# FC_GC_PCB.net
KiCad netlist of a schematic drawn in EasyEDA Pro
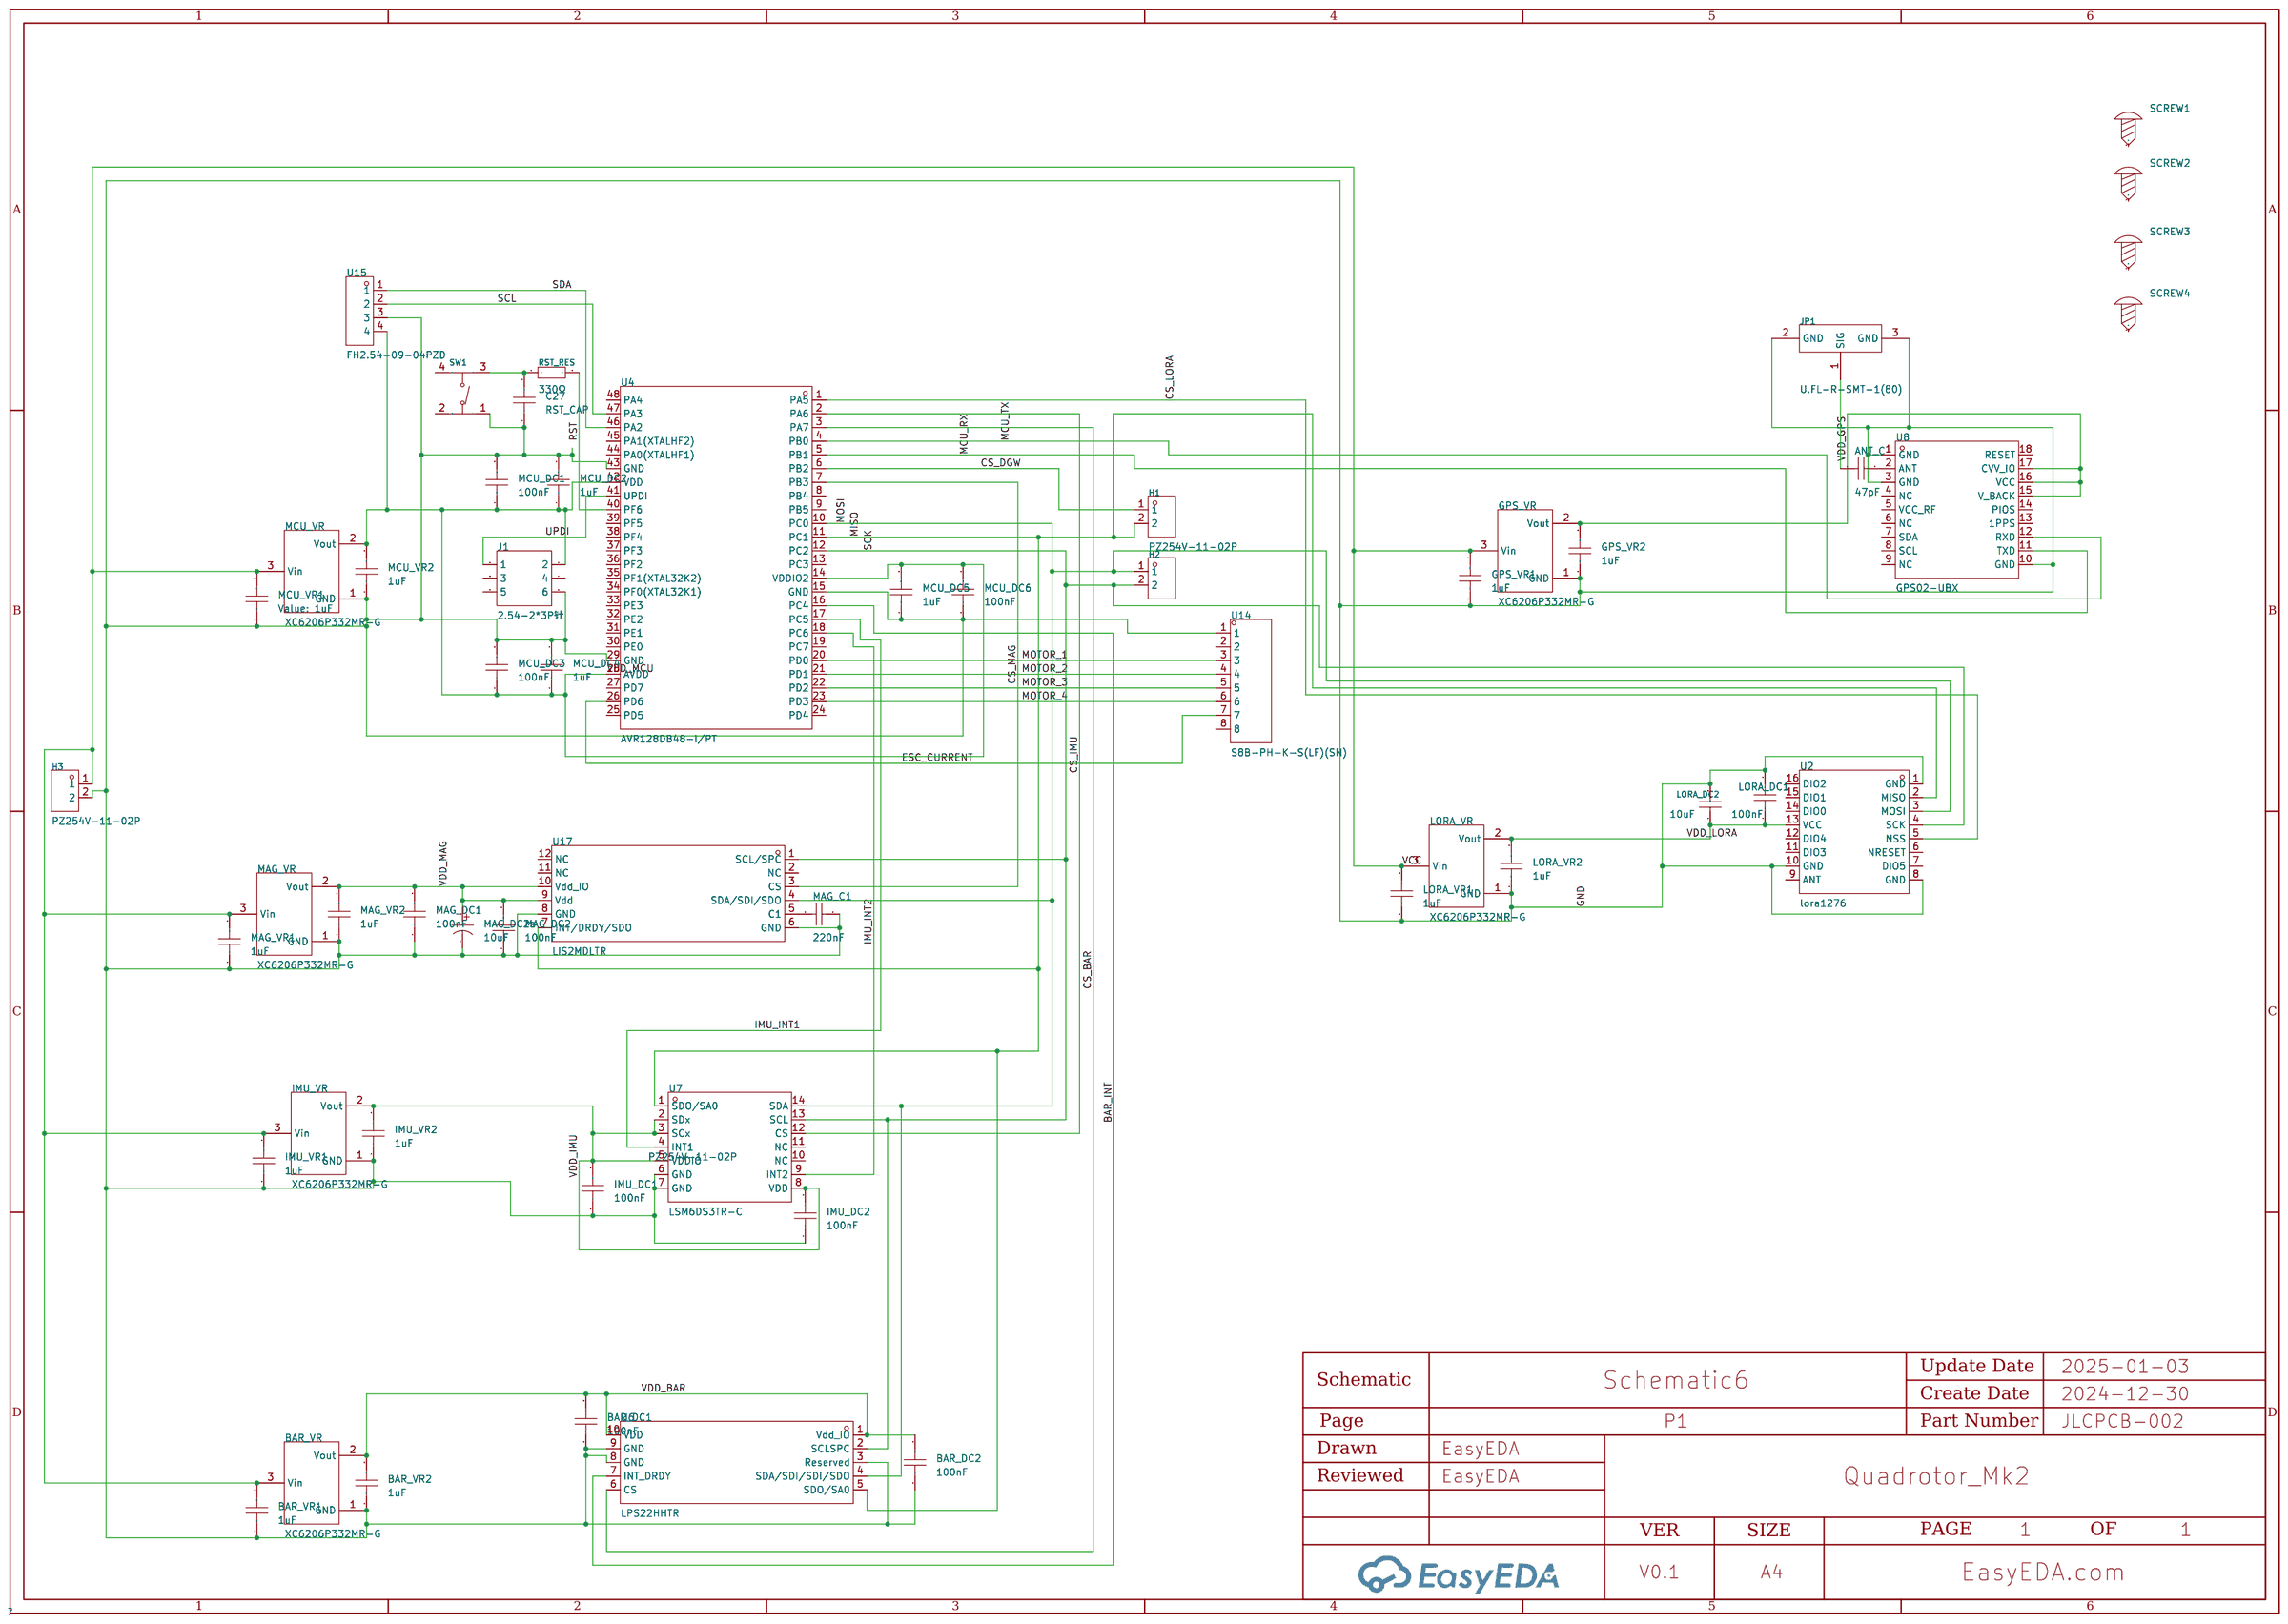
[diagram p0: schematic sheet]

(export (version "E")
  (design (tool "Eeschema 10.0.6"))
  (components
    (comp (ref "ANT_C")
      (value "47pF")
      (footprint "easyedapro:C0402")
      (fields (field (name "Manufacturer Part") "0402CG470J500NT") (field (name "Manufacturer") "FH(风华)"))
      (libsource (lib "easyedapro") (part "0402CG470J500NT"))
    )
    (comp (ref "BAR_DC1")
      (value "100nF")
      (footprint "easyedapro:C0402")
      (fields
        (field (name "Manufacturer Part") "CL05B104KO5NNNC")
        (field (name "Manufacturer") "SAMSUNG(三星)")
      )
      (libsource (lib "easyedapro") (part "CL05B104KO5NNNC"))
    )
    (comp (ref "BAR_DC2")
      (value "100nF")
      (footprint "easyedapro:C0402")
      (fields
        (field (name "Manufacturer Part") "CL05B104KO5NNNC")
        (field (name "Manufacturer") "SAMSUNG(三星)")
      )
      (libsource (lib "easyedapro") (part "CL05B104KO5NNNC"))
    )
    (comp (ref "BAR_VR")
      (value "XC6206P332MR-G")
      (footprint "easyedapro:SOT-23-3_L2.9-W1.6-P1.90-LS2.8-BR")
      (fields (field (name "Manufacturer") "TOREX(特瑞仕)"))
      (libsource (lib "easyedapro") (part "XC6206P332MR"))
    )
    (comp (ref "BAR_VR1")
      (value "1uF")
      (footprint "easyedapro:C0603")
      (fields
        (field (name "Manufacturer Part") "CL05A105KA5NQNC")
        (field (name "Manufacturer") "SAMSUNG(三星)")
      )
      (libsource (lib "easyedapro") (part "CL10A105KB8NNNC"))
    )
    (comp (ref "BAR_VR2")
      (value "1uF")
      (footprint "easyedapro:C0603")
      (fields
        (field (name "Manufacturer Part") "CL05A105KA5NQNC")
        (field (name "Manufacturer") "SAMSUNG(三星)")
      )
      (libsource (lib "easyedapro") (part "CL10A105KB8NNNC"))
    )
    (comp (ref "C27")
      (value "1uF")
      (footprint "easyedapro:C0603")
      (fields
        (field (name "Manufacturer Part") "CL10A105KB8NNNC")
        (field (name "Manufacturer") "SAMSUNG(三星)")
      )
      (libsource (lib "easyedapro") (part "CL10A105KB8NNNC"))
    )
    (comp (ref "GPS_VR")
      (value "XC6206P332MR-G")
      (footprint "easyedapro:SOT-23-3_L2.9-W1.6-P1.90-LS2.8-BR")
      (fields (field (name "Manufacturer") "TOREX(特瑞仕)"))
      (libsource (lib "easyedapro") (part "XC6206P332MR"))
    )
    (comp (ref "GPS_VR1")
      (value "1uF")
      (footprint "easyedapro:C0603")
      (fields
        (field (name "Manufacturer Part") "CL05A105KA5NQNC")
        (field (name "Manufacturer") "SAMSUNG(三星)")
      )
      (libsource (lib "easyedapro") (part "CL10A105KB8NNNC"))
    )
    (comp (ref "GPS_VR2")
      (value "1uF")
      (footprint "easyedapro:C0603")
      (fields
        (field (name "Manufacturer Part") "CL05A105KA5NQNC")
        (field (name "Manufacturer") "SAMSUNG(三星)")
      )
      (libsource (lib "easyedapro") (part "CL10A105KB8NNNC"))
    )
    (comp (ref "H1")
      (value "PZ254V-11-02P")
      (footprint "easyedapro:HDR-TH_2P-P2.54-V-M")
      (fields (field (name "Manufacturer") "XFCN(兴飞)"))
      (libsource (lib "easyedapro") (part "PZ254V-11-02P"))
    )
    (comp (ref "H2")
      (value "PZ254V-11-02P")
      (footprint "easyedapro:HDR-TH_2P-P2.54-V-M")
      (fields (field (name "Manufacturer") "XFCN(兴飞)"))
      (libsource (lib "easyedapro") (part "PZ254V-11-02P"))
    )
    (comp (ref "H3")
      (value "PZ254V-11-02P")
      (footprint "easyedapro:HDR-TH_2P-P2.54-V-M")
      (fields (field (name "Manufacturer") "XFCN(兴飞)"))
      (libsource (lib "easyedapro") (part "PZ254V-11-02P"))
    )
    (comp (ref "IMU_DC1")
      (value "100nF")
      (footprint "easyedapro:C0402")
      (fields
        (field (name "Manufacturer Part") "CL05B104KO5NNNC")
        (field (name "Manufacturer") "SAMSUNG(三星)")
      )
      (libsource (lib "easyedapro") (part "CL05B104KO5NNNC"))
    )
    (comp (ref "IMU_DC2")
      (value "100nF")
      (footprint "easyedapro:C0402")
      (fields
        (field (name "Manufacturer Part") "CL05B104KO5NNNC")
        (field (name "Manufacturer") "SAMSUNG(三星)")
      )
      (libsource (lib "easyedapro") (part "CL05B104KO5NNNC"))
    )
    (comp (ref "IMU_VR")
      (value "XC6206P332MR-G")
      (footprint "easyedapro:SOT-23-3_L2.9-W1.6-P1.90-LS2.8-BR")
      (fields (field (name "Manufacturer") "TOREX(特瑞仕)"))
      (libsource (lib "easyedapro") (part "XC6206P332MR"))
    )
    (comp (ref "IMU_VR1")
      (value "1uF")
      (footprint "easyedapro:C0603")
      (fields
        (field (name "Manufacturer Part") "CL05A105KA5NQNC")
        (field (name "Manufacturer") "SAMSUNG(三星)")
      )
      (libsource (lib "easyedapro") (part "CL10A105KB8NNNC"))
    )
    (comp (ref "IMU_VR2")
      (value "1uF")
      (footprint "easyedapro:C0603")
      (fields
        (field (name "Manufacturer Part") "CL05A105KA5NQNC")
        (field (name "Manufacturer") "SAMSUNG(三星)")
      )
      (libsource (lib "easyedapro") (part "CL10A105KB8NNNC"))
    )
    (comp (ref "J1")
      (value "2.54-2*3P针")
      (footprint "easyedapro:HDR-TH_6P-P2.54-V-M-R2-C3-S2.54-1")
      (fields (field (name "Manufacturer") "BOOMELE(博穆精密)"))
      (libsource (lib "easyedapro") (part "Header-Male-2.54_2x3"))
    )
    (comp (ref "JP1")
      (value "U.FL-R-SMT-1(80)")
      (footprint "easyedapro:RF-SMD_FRF05002-JSS103M")
      (fields (field (name "Manufacturer") "HRS(广濑)"))
      (libsource (lib "easyedapro") (part "U.FL-R-SMT-1(80)"))
    )
    (comp (ref "LORA_DC1")
      (value "100nF")
      (footprint "easyedapro:C0402")
      (fields
        (field (name "Manufacturer Part") "CL05B104KO5NNNC")
        (field (name "Manufacturer") "SAMSUNG(三星)")
      )
      (libsource (lib "easyedapro") (part "CL05B104KO5NNNC"))
    )
    (comp (ref "LORA_DC2")
      (value "10uF")
      (footprint "easyedapro:C0402")
      (fields
        (field (name "Manufacturer Part") "CL05A106MQ5NUNC")
        (field (name "Manufacturer") "SAMSUNG(三星)")
      )
      (libsource (lib "easyedapro") (part "CL05A106MQ5NUNC"))
    )
    (comp (ref "LORA_VR")
      (value "XC6206P332MR-G")
      (footprint "easyedapro:SOT-23-3_L2.9-W1.6-P1.90-LS2.8-BR")
      (fields (field (name "Manufacturer") "TOREX(特瑞仕)"))
      (libsource (lib "easyedapro") (part "XC6206P332MR"))
    )
    (comp (ref "LORA_VR1")
      (value "1uF")
      (footprint "easyedapro:C0603")
      (fields
        (field (name "Manufacturer Part") "CL05A105KA5NQNC")
        (field (name "Manufacturer") "SAMSUNG(三星)")
      )
      (libsource (lib "easyedapro") (part "CL10A105KB8NNNC"))
    )
    (comp (ref "LORA_VR2")
      (value "1uF")
      (footprint "easyedapro:C0603")
      (fields
        (field (name "Manufacturer Part") "CL05A105KA5NQNC")
        (field (name "Manufacturer") "SAMSUNG(三星)")
      )
      (libsource (lib "easyedapro") (part "CL10A105KB8NNNC"))
    )
    (comp (ref "MAG_C1")
      (value "220nF")
      (footprint "easyedapro:C0402")
      (fields
        (field (name "Manufacturer Part") "CL05B224KO5NNNC")
        (field (name "Manufacturer") "SAMSUNG(三星)")
      )
      (libsource (lib "easyedapro") (part "CL05B224KO5NNNC"))
    )
    (comp (ref "MAG_DC1")
      (value "100nF")
      (footprint "easyedapro:C0402")
      (fields
        (field (name "Manufacturer Part") "CL05B104KO5NNNC")
        (field (name "Manufacturer") "SAMSUNG(三星)")
      )
      (libsource (lib "easyedapro") (part "CL05B104KO5NNNC"))
    )
    (comp (ref "MAG_DC2")
      (value "100nF")
      (footprint "easyedapro:C0402")
      (fields
        (field (name "Manufacturer Part") "CL05B104KO5NNNC")
        (field (name "Manufacturer") "SAMSUNG(三星)")
      )
      (libsource (lib "easyedapro") (part "CL05B104KO5NNNC"))
    )
    (comp (ref "MAG_DC2a")
      (value "10uF")
      (fields (field (name "Manufacturer Part") "RVT1J100M0605") (field (name "Manufacturer") "ROQANG(容强)"))
      (libsource (lib "easyedapro") (part "HU2G100M-CRG12"))
    )
    (comp (ref "MAG_VR")
      (value "XC6206P332MR-G")
      (footprint "easyedapro:SOT-23-3_L2.9-W1.6-P1.90-LS2.8-BR")
      (fields (field (name "Manufacturer") "TOREX(特瑞仕)"))
      (libsource (lib "easyedapro") (part "XC6206P332MR"))
    )
    (comp (ref "MAG_VR1")
      (value "1uF")
      (footprint "easyedapro:C0603")
      (fields
        (field (name "Manufacturer Part") "CL05A105KA5NQNC")
        (field (name "Manufacturer") "SAMSUNG(三星)")
      )
      (libsource (lib "easyedapro") (part "CL10A105KB8NNNC"))
    )
    (comp (ref "MAG_VR2")
      (value "1uF")
      (footprint "easyedapro:C0603")
      (fields
        (field (name "Manufacturer Part") "CL05A105KA5NQNC")
        (field (name "Manufacturer") "SAMSUNG(三星)")
      )
      (libsource (lib "easyedapro") (part "CL10A105KB8NNNC"))
    )
    (comp (ref "MCU_DC1")
      (value "100nF")
      (footprint "easyedapro:C0402")
      (fields
        (field (name "Manufacturer Part") "CL05B104KO5NNNC")
        (field (name "Manufacturer") "SAMSUNG(三星)")
      )
      (libsource (lib "easyedapro") (part "CL05B104KO5NNNC"))
    )
    (comp (ref "MCU_DC2")
      (value "1uF")
      (footprint "easyedapro:C0603")
      (fields
        (field (name "Manufacturer Part") "CL05A105KA5NQNC")
        (field (name "Manufacturer") "SAMSUNG(三星)")
      )
      (libsource (lib "easyedapro") (part "CL10A105KB8NNNC"))
    )
    (comp (ref "MCU_DC3")
      (value "100nF")
      (footprint "easyedapro:C0402")
      (fields
        (field (name "Manufacturer Part") "CL05B104KO5NNNC")
        (field (name "Manufacturer") "SAMSUNG(三星)")
      )
      (libsource (lib "easyedapro") (part "CL05B104KO5NNNC"))
    )
    (comp (ref "MCU_DC4")
      (value "1uF")
      (footprint "easyedapro:C0603")
      (fields
        (field (name "Manufacturer Part") "CL05A105KA5NQNC")
        (field (name "Manufacturer") "SAMSUNG(三星)")
      )
      (libsource (lib "easyedapro") (part "CL10A105KB8NNNC"))
    )
    (comp (ref "MCU_DC5")
      (value "1uF")
      (footprint "easyedapro:C0603")
      (fields
        (field (name "Manufacturer Part") "CL05A105KA5NQNC")
        (field (name "Manufacturer") "SAMSUNG(三星)")
      )
      (libsource (lib "easyedapro") (part "CL10A105KB8NNNC"))
    )
    (comp (ref "MCU_DC6")
      (value "100nF")
      (footprint "easyedapro:C0402")
      (fields
        (field (name "Manufacturer Part") "CL05B104KO5NNNC")
        (field (name "Manufacturer") "SAMSUNG(三星)")
      )
      (libsource (lib "easyedapro") (part "CL05B104KO5NNNC"))
    )
    (comp (ref "MCU_VR")
      (value "XC6206P332MR-G")
      (footprint "easyedapro:SOT-23-3_L2.9-W1.6-P1.90-LS2.8-BR")
      (fields (field (name "Manufacturer") "TOREX(特瑞仕)"))
      (libsource (lib "easyedapro") (part "XC6206P332MR"))
    )
    (comp (ref "MCU_VR1")
      (value "1uF")
      (footprint "easyedapro:C0603")
      (fields
        (field (name "Manufacturer Part") "CL05A105KA5NQNC")
        (field (name "Manufacturer") "SAMSUNG(三星)")
      )
      (libsource (lib "easyedapro") (part "CL10A105KB8NNNC"))
    )
    (comp (ref "MCU_VR2")
      (value "1uF")
      (footprint "easyedapro:C0603")
      (fields
        (field (name "Manufacturer Part") "CL05A105KA5NQNC")
        (field (name "Manufacturer") "SAMSUNG(三星)")
      )
      (libsource (lib "easyedapro") (part "CL10A105KB8NNNC"))
    )
    (comp (ref "RST_RES")
      (value "330Ω")
      (footprint "easyedapro:R0402")
      (fields
        (field (name "Manufacturer Part") "0402WGF3300TCE")
        (field (name "Manufacturer") "UNI-ROYAL(厚声)")
      )
      (libsource (lib "easyedapro") (part "0402WGF3300TCE"))
    )
    (comp (ref "SCREW1")
      (value "~")
      (footprint "easyedapro:Screw-Hole-M2")
      (libsource (lib "easyedapro") (part "Screw-Hole"))
    )
    (comp (ref "SCREW2")
      (value "~")
      (footprint "easyedapro:Screw-Hole-M2")
      (libsource (lib "easyedapro") (part "Screw-Hole"))
    )
    (comp (ref "SCREW3")
      (value "~")
      (footprint "easyedapro:Screw-Hole-M2")
      (libsource (lib "easyedapro") (part "Screw-Hole"))
    )
    (comp (ref "SCREW4")
      (value "~")
      (footprint "easyedapro:Screw-Hole-M2")
      (libsource (lib "easyedapro") (part "Screw-Hole"))
    )
    (comp (ref "SW1")
      (value "TS-1187A-B-A-B")
      (footprint "easyedapro:SW-SMD_4P-L5.1-W5.1-P3.70-LS6.5-TL-2")
      (fields (field (name "Manufacturer") "XKB Connectivity(中国星坤)"))
      (libsource (lib "easyedapro") (part "TS-1187A-B-A-B"))
    )
    (comp (ref "U2")
      (value "lora1276")
      (footprint "easyedapro:COMM-SMD_LORA1276-C1-915MHZ")
      (description "Frequency:915MHz")
      (fields
        (field (name "Manufacturer Part") "lora1276-C1-915MHz")
        (field (name "Manufacturer") "G-NiceRF(思为无线)")
      )
      (libsource (lib "easyedapro") (part "LORA1276-C1-915MHZ"))
    )
    (comp (ref "U4")
      (value "AVR128DB48-I/PT")
      (footprint "easyedapro:TQFP-48_L7.0-W7.0-P0.50-LS9.0-BL")
      (fields (field (name "Manufacturer") "MICROCHIP(美国微芯)"))
      (libsource (lib "easyedapro") (part "AVR128DB48-I/PT"))
    )
    (comp (ref "U6")
      (value "LPS22HHTR")
      (footprint "easyedapro:HLGA-10L_LPS22HBTR")
      (fields (field (name "Manufacturer") "ST(意法半导体)"))
      (libsource (lib "easyedapro") (part "LPS22HHTR"))
    )
    (comp (ref "U7")
      (value "LSM6DS3TR-C")
      (footprint "easyedapro:LGA-14_L3.0-W2.5-P0.50-TL")
      (fields (field (name "Manufacturer") "ST(意法半导体)"))
      (libsource (lib "easyedapro") (part "LSM6DS3TR-C"))
    )
    (comp (ref "U8")
      (value "GPS02-UBX")
      (footprint "easyedapro:WIRELM-SMD_18P-L16.5-W14.5_P1.80-TL")
      (fields (field (name "Manufacturer") "G-NiceRF(思为无线)"))
      (libsource (lib "easyedapro") (part "GPS02-UBX"))
    )
    (comp (ref "U14")
      (value "S8B-PH-K-S(LF)(SN)")
      (footprint "easyedapro:CONN-TH_S8B-PH-K-S-LF-SN")
      (fields (field (name "Manufacturer") "JST"))
      (libsource (lib "easyedapro") (part "S8B-PH-K-S-(LF)(SN)"))
    )
    (comp (ref "U15")
      (value "FH2.54-09-04PZD")
      (footprint "easyedapro:HDR-TH_4P-P2.54-V-F")
      (fields (field (name "Manufacturer") "XUNPU(讯普)"))
      (libsource (lib "easyedapro") (part "FH2.54-09-04PZD"))
    )
    (comp (ref "U17")
      (value "LIS2MDLTR")
      (footprint "easyedapro:LGA-12_L2.0-W2.0-P0.50-BL")
      (fields (field (name "Manufacturer") "ST(意法半导体)"))
      (libsource (lib "easyedapro") (part "LIS2MDLTR"))
    )
  )
  (nets
    (net (code "1") (name "/BAR_INT") (class "Default")
      (node (ref "U4") (pin "16") (pinfunction "PC4_16") (pintype "unspecified"))
      (node (ref "U6") (pin "7") (pinfunction "INT_DRDY_7") (pintype "input"))
    )
    (net (code "2") (name "/CS_BAR") (class "Default")
      (node (ref "U4") (pin "3") (pinfunction "PA7_3") (pintype "unspecified"))
      (node (ref "U6") (pin "6") (pinfunction "CS_6") (pintype "input"))
    )
    (net (code "3") (name "/CS_DGW") (class "Default")
      (node (ref "H1") (pin "1") (pinfunction "1_1") (pintype "input"))
      (node (ref "U4") (pin "6") (pinfunction "PB2_6") (pintype "unspecified"))
    )
    (net (code "4") (name "/CS_IMU") (class "Default")
      (node (ref "U4") (pin "2") (pinfunction "PA6_2") (pintype "unspecified"))
      (node (ref "U7") (pin "12") (pinfunction "CS_12") (pintype "unspecified"))
    )
    (net (code "5") (name "/CS_LORA") (class "Default")
      (node (ref "U2") (pin "5") (pinfunction "NSS_5") (pintype "unspecified"))
      (node (ref "U4") (pin "1") (pinfunction "PA5_1") (pintype "unspecified"))
    )
    (net (code "6") (name "/CS_MAG") (class "Default")
      (node (ref "U17") (pin "3") (pinfunction "CS_3") (pintype "unspecified"))
      (node (ref "U4") (pin "7") (pinfunction "PB3_7") (pintype "unspecified"))
    )
    (net (code "7") (name "/ESC_CURRENT") (class "Default")
      (node (ref "U14") (pin "7") (pinfunction "7_7") (pintype "unspecified"))
      (node (ref "U4") (pin "26") (pinfunction "PD6_26") (pintype "unspecified"))
    )
    (net (code "8") (name "/GND") (class "Default")
      (node (ref "BAR_DC1") (pin "1") (pinfunction "1_1") (pintype "unspecified"))
      (node (ref "BAR_DC2") (pin "1") (pinfunction "1_1") (pintype "unspecified"))
      (node (ref "BAR_VR") (pin "1") (pinfunction "GND_1") (pintype "unspecified"))
      (node (ref "BAR_VR1") (pin "1") (pinfunction "1_1") (pintype "unspecified"))
      (node (ref "BAR_VR2") (pin "1") (pinfunction "1_1") (pintype "unspecified"))
      (node (ref "C27") (pin "1") (pinfunction "1_1") (pintype "unspecified"))
      (node (ref "GPS_VR") (pin "1") (pinfunction "GND_1") (pintype "unspecified"))
      (node (ref "GPS_VR1") (pin "1") (pinfunction "1_1") (pintype "unspecified"))
      (node (ref "GPS_VR2") (pin "1") (pinfunction "1_1") (pintype "unspecified"))
      (node (ref "H3") (pin "2") (pinfunction "2_2") (pintype "input"))
      (node (ref "IMU_DC1") (pin "1") (pinfunction "1_1") (pintype "unspecified"))
      (node (ref "IMU_DC2") (pin "1") (pinfunction "1_1") (pintype "unspecified"))
      (node (ref "IMU_VR") (pin "1") (pinfunction "GND_1") (pintype "unspecified"))
      (node (ref "IMU_VR1") (pin "1") (pinfunction "1_1") (pintype "unspecified"))
      (node (ref "IMU_VR2") (pin "1") (pinfunction "1_1") (pintype "unspecified"))
      (node (ref "J1") (pin "6") (pinfunction "6_6") (pintype "input"))
      (node (ref "JP1") (pin "2") (pinfunction "GND_2") (pintype "input"))
      (node (ref "JP1") (pin "3") (pinfunction "GND_3") (pintype "input"))
      (node (ref "LORA_DC1") (pin "2") (pinfunction "2_2") (pintype "unspecified"))
      (node (ref "LORA_DC2") (pin "2") (pinfunction "2_2") (pintype "input"))
      (node (ref "LORA_VR") (pin "1") (pinfunction "GND_1") (pintype "unspecified"))
      (node (ref "LORA_VR1") (pin "1") (pinfunction "1_1") (pintype "unspecified"))
      (node (ref "LORA_VR2") (pin "1") (pinfunction "1_1") (pintype "unspecified"))
      (node (ref "MAG_C1") (pin "2") (pinfunction "2_2") (pintype "input"))
      (node (ref "MAG_DC1") (pin "1") (pinfunction "1_1") (pintype "unspecified"))
      (node (ref "MAG_DC2") (pin "1") (pinfunction "1_1") (pintype "unspecified"))
      (node (ref "MAG_DC2a") (pin "2") (pinfunction "2_2") (pintype "input"))
      (node (ref "MAG_VR") (pin "1") (pinfunction "GND_1") (pintype "unspecified"))
      (node (ref "MAG_VR1") (pin "1") (pinfunction "1_1") (pintype "unspecified"))
      (node (ref "MAG_VR2") (pin "1") (pinfunction "1_1") (pintype "unspecified"))
      (node (ref "MCU_DC1") (pin "2") (pinfunction "2_2") (pintype "unspecified"))
      (node (ref "MCU_DC2") (pin "2") (pinfunction "2_2") (pintype "unspecified"))
      (node (ref "MCU_DC3") (pin "2") (pinfunction "2_2") (pintype "unspecified"))
      (node (ref "MCU_DC4") (pin "2") (pinfunction "2_2") (pintype "unspecified"))
      (node (ref "MCU_DC5") (pin "1") (pinfunction "1_1") (pintype "unspecified"))
      (node (ref "MCU_DC6") (pin "1") (pinfunction "1_1") (pintype "unspecified"))
      (node (ref "MCU_VR") (pin "1") (pinfunction "GND_1") (pintype "unspecified"))
      (node (ref "MCU_VR1") (pin "1") (pinfunction "1_1") (pintype "unspecified"))
      (node (ref "MCU_VR2") (pin "1") (pinfunction "1_1") (pintype "unspecified"))
      (node (ref "SW1") (pin "1") (pinfunction "A_1") (pintype "input"))
      (node (ref "U14") (pin "1") (pinfunction "1_1") (pintype "unspecified"))
      (node (ref "U15") (pin "3") (pinfunction "3_3") (pintype "unspecified"))
      (node (ref "U17") (pin "6") (pinfunction "GND_6") (pintype "unspecified"))
      (node (ref "U17") (pin "8") (pinfunction "GND_8") (pintype "unspecified"))
      (node (ref "U2") (pin "1") (pinfunction "GND_1") (pintype "unspecified"))
      (node (ref "U2") (pin "10") (pinfunction "GND_10") (pintype "unspecified"))
      (node (ref "U2") (pin "8") (pinfunction "GND_8") (pintype "unspecified"))
      (node (ref "U4") (pin "15") (pinfunction "GND_15") (pintype "unspecified"))
      (node (ref "U4") (pin "29") (pinfunction "GND_29") (pintype "unspecified"))
      (node (ref "U4") (pin "43") (pinfunction "GND_43") (pintype "unspecified"))
      (node (ref "U6") (pin "3") (pinfunction "Reserved_3") (pintype "input"))
      (node (ref "U6") (pin "8") (pinfunction "GND_8") (pintype "input"))
      (node (ref "U6") (pin "9") (pinfunction "GND_9") (pintype "input"))
      (node (ref "U7") (pin "6") (pinfunction "GND_6") (pintype "unspecified"))
      (node (ref "U7") (pin "7") (pinfunction "GND_7") (pintype "unspecified"))
      (node (ref "U8") (pin "1") (pinfunction "GND_1") (pintype "unspecified"))
      (node (ref "U8") (pin "10") (pinfunction "GND_10") (pintype "unspecified"))
      (node (ref "U8") (pin "3") (pinfunction "GND_3") (pintype "unspecified"))
    )
    (net (code "9") (name "/IMU_INT1") (class "Default")
      (node (ref "U4") (pin "17") (pinfunction "PC5_17") (pintype "unspecified"))
      (node (ref "U7") (pin "4") (pinfunction "INT1_4") (pintype "unspecified"))
    )
    (net (code "10") (name "/IMU_INT2") (class "Default")
      (node (ref "U4") (pin "18") (pinfunction "PC6_18") (pintype "unspecified"))
      (node (ref "U7") (pin "9") (pinfunction "INT2_9") (pintype "unspecified"))
    )
    (net (code "11") (name "/MCU_RX") (class "Default")
      (node (ref "U4") (pin "5") (pinfunction "PB1_5") (pintype "unspecified"))
      (node (ref "U8") (pin "11") (pinfunction "TXD_11") (pintype "unspecified"))
    )
    (net (code "12") (name "/MCU_TX") (class "Default")
      (node (ref "U4") (pin "4") (pinfunction "PB0_4") (pintype "unspecified"))
      (node (ref "U8") (pin "12") (pinfunction "RXD_12") (pintype "unspecified"))
    )
    (net (code "13") (name "/MISO") (class "Default")
      (node (ref "H1") (pin "2") (pinfunction "2_2") (pintype "input"))
      (node (ref "U17") (pin "7") (pinfunction "INT/DRDY/SDO_7") (pintype "unspecified"))
      (node (ref "U2") (pin "2") (pinfunction "MISO_2") (pintype "unspecified"))
      (node (ref "U4") (pin "11") (pinfunction "PC1_11") (pintype "unspecified"))
      (node (ref "U6") (pin "5") (pinfunction "SDO/SA0_5") (pintype "input"))
      (node (ref "U7") (pin "1") (pinfunction "SDO/SA0_1") (pintype "unspecified"))
    )
    (net (code "14") (name "/MOSI") (class "Default")
      (node (ref "H2") (pin "1") (pinfunction "1_1") (pintype "input"))
      (node (ref "U17") (pin "4") (pinfunction "SDA/SDI/SDO_4") (pintype "unspecified"))
      (node (ref "U2") (pin "3") (pinfunction "MOSI_3") (pintype "unspecified"))
      (node (ref "U4") (pin "10") (pinfunction "PC0_10") (pintype "unspecified"))
      (node (ref "U6") (pin "4") (pinfunction "SDA/SDI/SDI/SDO_4") (pintype "input"))
      (node (ref "U7") (pin "14") (pinfunction "SDA_14") (pintype "unspecified"))
    )
    (net (code "15") (name "/MOTOR_1") (class "Default")
      (node (ref "U14") (pin "3") (pinfunction "3_3") (pintype "unspecified"))
      (node (ref "U4") (pin "20") (pinfunction "PD0_20") (pintype "unspecified"))
    )
    (net (code "16") (name "/MOTOR_2") (class "Default")
      (node (ref "U14") (pin "4") (pinfunction "4_4") (pintype "unspecified"))
      (node (ref "U4") (pin "21") (pinfunction "PD1_21") (pintype "unspecified"))
    )
    (net (code "17") (name "/MOTOR_3") (class "Default")
      (node (ref "U14") (pin "5") (pinfunction "5_5") (pintype "unspecified"))
      (node (ref "U4") (pin "22") (pinfunction "PD2_22") (pintype "unspecified"))
    )
    (net (code "18") (name "/MOTOR_4") (class "Default")
      (node (ref "U14") (pin "6") (pinfunction "6_6") (pintype "unspecified"))
      (node (ref "U4") (pin "23") (pinfunction "PD3_23") (pintype "unspecified"))
    )
    (net (code "19") (name "/RST") (class "Default")
      (node (ref "RST_RES") (pin "2") (pinfunction "2_2") (pintype "input"))
      (node (ref "U4") (pin "40") (pinfunction "PF6_40") (pintype "unspecified"))
    )
    (net (code "20") (name "/SCK") (class "Default")
      (node (ref "H2") (pin "2") (pinfunction "2_2") (pintype "input"))
      (node (ref "U17") (pin "1") (pinfunction "SCL/SPC_1") (pintype "unspecified"))
      (node (ref "U2") (pin "4") (pinfunction "SCK_4") (pintype "unspecified"))
      (node (ref "U4") (pin "12") (pinfunction "PC2_12") (pintype "unspecified"))
      (node (ref "U6") (pin "2") (pinfunction "SCLSPC_2") (pintype "input"))
      (node (ref "U7") (pin "13") (pinfunction "SCL_13") (pintype "unspecified"))
    )
    (net (code "21") (name "/SCL") (class "Default")
      (node (ref "U15") (pin "2") (pinfunction "2_2") (pintype "unspecified"))
      (node (ref "U4") (pin "47") (pinfunction "PA3_47") (pintype "unspecified"))
    )
    (net (code "22") (name "/SDA") (class "Default")
      (node (ref "U15") (pin "1") (pinfunction "1_1") (pintype "unspecified"))
      (node (ref "U4") (pin "46") (pinfunction "PA2_46") (pintype "unspecified"))
    )
    (net (code "23") (name "/UPDI") (class "Default")
      (node (ref "J1") (pin "1") (pinfunction "1_1") (pintype "input"))
      (node (ref "U4") (pin "41") (pinfunction "UPDI_41") (pintype "unspecified"))
    )
    (net (code "24") (name "/VCC") (class "Default")
      (node (ref "BAR_VR") (pin "3") (pinfunction "Vin_3") (pintype "unspecified"))
      (node (ref "BAR_VR1") (pin "2") (pinfunction "2_2") (pintype "unspecified"))
      (node (ref "GPS_VR") (pin "3") (pinfunction "Vin_3") (pintype "unspecified"))
      (node (ref "GPS_VR1") (pin "2") (pinfunction "2_2") (pintype "unspecified"))
      (node (ref "H3") (pin "1") (pinfunction "1_1") (pintype "input"))
      (node (ref "IMU_VR") (pin "3") (pinfunction "Vin_3") (pintype "unspecified"))
      (node (ref "IMU_VR1") (pin "2") (pinfunction "2_2") (pintype "unspecified"))
      (node (ref "LORA_VR") (pin "3") (pinfunction "Vin_3") (pintype "unspecified"))
      (node (ref "LORA_VR1") (pin "2") (pinfunction "2_2") (pintype "unspecified"))
      (node (ref "MAG_VR") (pin "3") (pinfunction "Vin_3") (pintype "unspecified"))
      (node (ref "MAG_VR1") (pin "2") (pinfunction "2_2") (pintype "unspecified"))
      (node (ref "MCU_VR") (pin "3") (pinfunction "Vin_3") (pintype "unspecified"))
      (node (ref "MCU_VR1") (pin "2") (pinfunction "2_2") (pintype "unspecified"))
    )
    (net (code "25") (name "/VDD_BAR") (class "Default")
      (node (ref "BAR_DC1") (pin "2") (pinfunction "2_2") (pintype "unspecified"))
      (node (ref "BAR_DC2") (pin "2") (pinfunction "2_2") (pintype "unspecified"))
      (node (ref "BAR_VR") (pin "2") (pinfunction "Vout_2") (pintype "unspecified"))
      (node (ref "BAR_VR2") (pin "2") (pinfunction "2_2") (pintype "unspecified"))
      (node (ref "U6") (pin "1") (pinfunction "Vdd_IO_1") (pintype "input"))
      (node (ref "U6") (pin "10") (pinfunction "VDD_10") (pintype "input"))
    )
    (net (code "26") (name "/VDD_GPS") (class "Default")
      (node (ref "GPS_VR") (pin "2") (pinfunction "Vout_2") (pintype "unspecified"))
      (node (ref "GPS_VR2") (pin "2") (pinfunction "2_2") (pintype "unspecified"))
      (node (ref "U8") (pin "15") (pinfunction "V_BACK_15") (pintype "unspecified"))
      (node (ref "U8") (pin "16") (pinfunction "VCC_16") (pintype "unspecified"))
      (node (ref "U8") (pin "17") (pinfunction "CVV_IO_17") (pintype "unspecified"))
    )
    (net (code "27") (name "/VDD_IMU") (class "Default")
      (node (ref "IMU_DC1") (pin "2") (pinfunction "2_2") (pintype "unspecified"))
      (node (ref "IMU_DC2") (pin "2") (pinfunction "2_2") (pintype "unspecified"))
      (node (ref "IMU_VR") (pin "2") (pinfunction "Vout_2") (pintype "unspecified"))
      (node (ref "IMU_VR2") (pin "2") (pinfunction "2_2") (pintype "unspecified"))
      (node (ref "U7") (pin "2") (pinfunction "SDx_2") (pintype "unspecified"))
      (node (ref "U7") (pin "3") (pinfunction "SCx_3") (pintype "unspecified"))
      (node (ref "U7") (pin "5") (pinfunction "VDDIO_5") (pintype "unspecified"))
      (node (ref "U7") (pin "8") (pinfunction "VDD_8") (pintype "unspecified"))
    )
    (net (code "28") (name "/VDD_LORA") (class "Default")
      (node (ref "LORA_DC1") (pin "1") (pinfunction "1_1") (pintype "unspecified"))
      (node (ref "LORA_DC2") (pin "1") (pinfunction "1_1") (pintype "input"))
      (node (ref "LORA_VR") (pin "2") (pinfunction "Vout_2") (pintype "unspecified"))
      (node (ref "LORA_VR2") (pin "2") (pinfunction "2_2") (pintype "unspecified"))
      (node (ref "U2") (pin "13") (pinfunction "VCC_13") (pintype "unspecified"))
    )
    (net (code "29") (name "/VDD_MAG") (class "Default")
      (node (ref "MAG_DC1") (pin "2") (pinfunction "2_2") (pintype "unspecified"))
      (node (ref "MAG_DC2") (pin "2") (pinfunction "2_2") (pintype "unspecified"))
      (node (ref "MAG_DC2a") (pin "1") (pinfunction "1_1") (pintype "input"))
      (node (ref "MAG_VR") (pin "2") (pinfunction "Vout_2") (pintype "unspecified"))
      (node (ref "MAG_VR2") (pin "2") (pinfunction "2_2") (pintype "unspecified"))
      (node (ref "U17") (pin "10") (pinfunction "Vdd_IO_10") (pintype "unspecified"))
      (node (ref "U17") (pin "9") (pinfunction "Vdd_9") (pintype "unspecified"))
    )
    (net (code "30") (name "/VDD_MCU") (class "Default")
      (node (ref "J1") (pin "2") (pinfunction "2_2") (pintype "input"))
      (node (ref "MCU_DC1") (pin "1") (pinfunction "1_1") (pintype "unspecified"))
      (node (ref "MCU_DC2") (pin "1") (pinfunction "1_1") (pintype "unspecified"))
      (node (ref "MCU_DC3") (pin "1") (pinfunction "1_1") (pintype "unspecified"))
      (node (ref "MCU_DC4") (pin "1") (pinfunction "1_1") (pintype "unspecified"))
      (node (ref "MCU_DC5") (pin "2") (pinfunction "2_2") (pintype "unspecified"))
      (node (ref "MCU_DC6") (pin "2") (pinfunction "2_2") (pintype "unspecified"))
      (node (ref "MCU_VR") (pin "2") (pinfunction "Vout_2") (pintype "unspecified"))
      (node (ref "MCU_VR2") (pin "2") (pinfunction "2_2") (pintype "unspecified"))
      (node (ref "U15") (pin "4") (pinfunction "4_4") (pintype "unspecified"))
      (node (ref "U4") (pin "14") (pinfunction "VDDIO2_14") (pintype "unspecified"))
      (node (ref "U4") (pin "28") (pinfunction "AVDD_28") (pintype "unspecified"))
      (node (ref "U4") (pin "42") (pinfunction "VDD_42") (pintype "unspecified"))
    )
    (net (code "31") (name "Net-(JP1-SIG)") (class "Default")
      (node (ref "ANT_C") (pin "1") (pinfunction "1_1") (pintype "input"))
      (node (ref "JP1") (pin "1") (pinfunction "SIG_1") (pintype "input"))
    )
    (net (code "32") (name "Net-(SW1-C)") (class "Default")
      (node (ref "C27") (pin "2") (pinfunction "2_2") (pintype "unspecified"))
      (node (ref "RST_RES") (pin "1") (pinfunction "1_1") (pintype "input"))
      (node (ref "SW1") (pin "3") (pinfunction "C_3") (pintype "input"))
    )
    (net (code "33") (name "Net-(U8-ANT)") (class "Default")
      (node (ref "ANT_C") (pin "2") (pinfunction "2_2") (pintype "input"))
      (node (ref "U8") (pin "2") (pinfunction "ANT_2") (pintype "unspecified"))
    )
    (net (code "34") (name "Net-(U17-C1)") (class "Default")
      (node (ref "MAG_C1") (pin "1") (pinfunction "1_1") (pintype "input"))
      (node (ref "U17") (pin "5") (pinfunction "C1_5") (pintype "unspecified"))
    )
    (net (code "35") (name "unconnected-(J1-Pad3)") (class "Default")
      (node (ref "J1") (pin "3") (pinfunction "3_3") (pintype "input"))
    )
    (net (code "36") (name "unconnected-(J1-Pad4)") (class "Default")
      (node (ref "J1") (pin "4") (pinfunction "4_4") (pintype "input"))
    )
    (net (code "37") (name "unconnected-(J1-Pad5)") (class "Default")
      (node (ref "J1") (pin "5") (pinfunction "5_5") (pintype "input"))
    )
    (net (code "38") (name "unconnected-(SCREW1-Pad1)") (class "Default")
      (node (ref "SCREW1") (pin "1") (pinfunction "1_1") (pintype "input"))
    )
    (net (code "39") (name "unconnected-(SCREW2-Pad1)") (class "Default")
      (node (ref "SCREW2") (pin "1") (pinfunction "1_1") (pintype "input"))
    )
    (net (code "40") (name "unconnected-(SCREW3-Pad1)") (class "Default")
      (node (ref "SCREW3") (pin "1") (pinfunction "1_1") (pintype "input"))
    )
    (net (code "41") (name "unconnected-(SCREW4-Pad1)") (class "Default")
      (node (ref "SCREW4") (pin "1") (pinfunction "1_1") (pintype "input"))
    )
    (net (code "42") (name "unconnected-(SW1-B-Pad2)") (class "Default")
      (node (ref "SW1") (pin "2") (pinfunction "B_2") (pintype "input"))
    )
    (net (code "43") (name "unconnected-(SW1-D-Pad4)") (class "Default")
      (node (ref "SW1") (pin "4") (pinfunction "D_4") (pintype "input"))
    )
    (net (code "44") (name "unconnected-(U2-ANT-Pad9)") (class "Default")
      (node (ref "U2") (pin "9") (pinfunction "ANT_9") (pintype "unspecified"))
    )
    (net (code "45") (name "unconnected-(U2-DIO0-Pad14)") (class "Default")
      (node (ref "U2") (pin "14") (pinfunction "DIO0_14") (pintype "unspecified"))
    )
    (net (code "46") (name "unconnected-(U2-DIO1-Pad15)") (class "Default")
      (node (ref "U2") (pin "15") (pinfunction "DIO1_15") (pintype "unspecified"))
    )
    (net (code "47") (name "unconnected-(U2-DIO2-Pad16)") (class "Default")
      (node (ref "U2") (pin "16") (pinfunction "DIO2_16") (pintype "unspecified"))
    )
    (net (code "48") (name "unconnected-(U2-DIO3-Pad11)") (class "Default")
      (node (ref "U2") (pin "11") (pinfunction "DIO3_11") (pintype "unspecified"))
    )
    (net (code "49") (name "unconnected-(U2-DIO4-Pad12)") (class "Default")
      (node (ref "U2") (pin "12") (pinfunction "DIO4_12") (pintype "unspecified"))
    )
    (net (code "50") (name "unconnected-(U2-DIO5-Pad7)") (class "Default")
      (node (ref "U2") (pin "7") (pinfunction "DIO5_7") (pintype "unspecified"))
    )
    (net (code "51") (name "unconnected-(U2-NRESET-Pad6)") (class "Default")
      (node (ref "U2") (pin "6") (pinfunction "NRESET_6") (pintype "unspecified"))
    )
    (net (code "52") (name "unconnected-(U4-PA0(XTALHF1)-Pad44)") (class "Default")
      (node (ref "U4") (pin "44") (pinfunction "PA0(XTALHF1)_44") (pintype "unspecified"))
    )
    (net (code "53") (name "unconnected-(U4-PA1(XTALHF2)-Pad45)") (class "Default")
      (node (ref "U4") (pin "45") (pinfunction "PA1(XTALHF2)_45") (pintype "unspecified"))
    )
    (net (code "54") (name "unconnected-(U4-PA4-Pad48)") (class "Default")
      (node (ref "U4") (pin "48") (pinfunction "PA4_48") (pintype "unspecified"))
    )
    (net (code "55") (name "unconnected-(U4-PB4-Pad8)") (class "Default")
      (node (ref "U4") (pin "8") (pinfunction "PB4_8") (pintype "unspecified"))
    )
    (net (code "56") (name "unconnected-(U4-PB5-Pad9)") (class "Default")
      (node (ref "U4") (pin "9") (pinfunction "PB5_9") (pintype "unspecified"))
    )
    (net (code "57") (name "unconnected-(U4-PC3-Pad13)") (class "Default")
      (node (ref "U4") (pin "13") (pinfunction "PC3_13") (pintype "unspecified"))
    )
    (net (code "58") (name "unconnected-(U4-PC7-Pad19)") (class "Default")
      (node (ref "U4") (pin "19") (pinfunction "PC7_19") (pintype "unspecified"))
    )
    (net (code "59") (name "unconnected-(U4-PD4-Pad24)") (class "Default")
      (node (ref "U4") (pin "24") (pinfunction "PD4_24") (pintype "unspecified"))
    )
    (net (code "60") (name "unconnected-(U4-PD5-Pad25)") (class "Default")
      (node (ref "U4") (pin "25") (pinfunction "PD5_25") (pintype "unspecified"))
    )
    (net (code "61") (name "unconnected-(U4-PD7-Pad27)") (class "Default")
      (node (ref "U4") (pin "27") (pinfunction "PD7_27") (pintype "unspecified"))
    )
    (net (code "62") (name "unconnected-(U4-PE0-Pad30)") (class "Default")
      (node (ref "U4") (pin "30") (pinfunction "PE0_30") (pintype "unspecified"))
    )
    (net (code "63") (name "unconnected-(U4-PE1-Pad31)") (class "Default")
      (node (ref "U4") (pin "31") (pinfunction "PE1_31") (pintype "unspecified"))
    )
    (net (code "64") (name "unconnected-(U4-PE2-Pad32)") (class "Default")
      (node (ref "U4") (pin "32") (pinfunction "PE2_32") (pintype "unspecified"))
    )
    (net (code "65") (name "unconnected-(U4-PE3-Pad33)") (class "Default")
      (node (ref "U4") (pin "33") (pinfunction "PE3_33") (pintype "unspecified"))
    )
    (net (code "66") (name "unconnected-(U4-PF0(XTAL32K1)-Pad34)") (class "Default")
      (node (ref "U4") (pin "34") (pinfunction "PF0(XTAL32K1)_34") (pintype "unspecified"))
    )
    (net (code "67") (name "unconnected-(U4-PF1(XTAL32K2)-Pad35)") (class "Default")
      (node (ref "U4") (pin "35") (pinfunction "PF1(XTAL32K2)_35") (pintype "unspecified"))
    )
    (net (code "68") (name "unconnected-(U4-PF2-Pad36)") (class "Default")
      (node (ref "U4") (pin "36") (pinfunction "PF2_36") (pintype "unspecified"))
    )
    (net (code "69") (name "unconnected-(U4-PF3-Pad37)") (class "Default")
      (node (ref "U4") (pin "37") (pinfunction "PF3_37") (pintype "unspecified"))
    )
    (net (code "70") (name "unconnected-(U4-PF4-Pad38)") (class "Default")
      (node (ref "U4") (pin "38") (pinfunction "PF4_38") (pintype "unspecified"))
    )
    (net (code "71") (name "unconnected-(U4-PF5-Pad39)") (class "Default")
      (node (ref "U4") (pin "39") (pinfunction "PF5_39") (pintype "unspecified"))
    )
    (net (code "72") (name "unconnected-(U7-NC-Pad10)") (class "Default")
      (node (ref "U7") (pin "10") (pinfunction "NC_10") (pintype "unspecified"))
    )
    (net (code "73") (name "unconnected-(U7-NC-Pad11)") (class "Default")
      (node (ref "U7") (pin "11") (pinfunction "NC_11") (pintype "unspecified"))
    )
    (net (code "74") (name "unconnected-(U8-1PPS-Pad13)") (class "Default")
      (node (ref "U8") (pin "13") (pinfunction "1PPS_13") (pintype "unspecified"))
    )
    (net (code "75") (name "unconnected-(U8-NC-Pad4)") (class "Default")
      (node (ref "U8") (pin "4") (pinfunction "NC_4") (pintype "unspecified"))
    )
    (net (code "76") (name "unconnected-(U8-NC-Pad6)") (class "Default")
      (node (ref "U8") (pin "6") (pinfunction "NC_6") (pintype "unspecified"))
    )
    (net (code "77") (name "unconnected-(U8-NC-Pad9)") (class "Default")
      (node (ref "U8") (pin "9") (pinfunction "NC_9") (pintype "unspecified"))
    )
    (net (code "78") (name "unconnected-(U8-PIOS-Pad14)") (class "Default")
      (node (ref "U8") (pin "14") (pinfunction "PIOS_14") (pintype "unspecified"))
    )
    (net (code "79") (name "unconnected-(U8-RESET-Pad18)") (class "Default")
      (node (ref "U8") (pin "18") (pinfunction "RESET_18") (pintype "unspecified"))
    )
    (net (code "80") (name "unconnected-(U8-SCL-Pad8)") (class "Default")
      (node (ref "U8") (pin "8") (pinfunction "SCL_8") (pintype "unspecified"))
    )
    (net (code "81") (name "unconnected-(U8-SDA-Pad7)") (class "Default")
      (node (ref "U8") (pin "7") (pinfunction "SDA_7") (pintype "unspecified"))
    )
    (net (code "82") (name "unconnected-(U8-VCC_RF-Pad5)") (class "Default")
      (node (ref "U8") (pin "5") (pinfunction "VCC_RF_5") (pintype "unspecified"))
    )
    (net (code "83") (name "unconnected-(U14-Pad2)") (class "Default")
      (node (ref "U14") (pin "2") (pinfunction "2_2") (pintype "unspecified"))
    )
    (net (code "84") (name "unconnected-(U14-Pad8)") (class "Default")
      (node (ref "U14") (pin "8") (pinfunction "8_8") (pintype "unspecified"))
    )
    (net (code "85") (name "unconnected-(U17-NC-Pad2)") (class "Default")
      (node (ref "U17") (pin "2") (pinfunction "NC_2") (pintype "unspecified"))
    )
    (net (code "86") (name "unconnected-(U17-NC-Pad11)") (class "Default")
      (node (ref "U17") (pin "11") (pinfunction "NC_11") (pintype "unspecified"))
    )
    (net (code "87") (name "unconnected-(U17-NC-Pad12)") (class "Default")
      (node (ref "U17") (pin "12") (pinfunction "NC_12") (pintype "unspecified"))
    )
  )
)
